# Drivers.net
KiCad netlist of a schematic drawn in Altium Designer
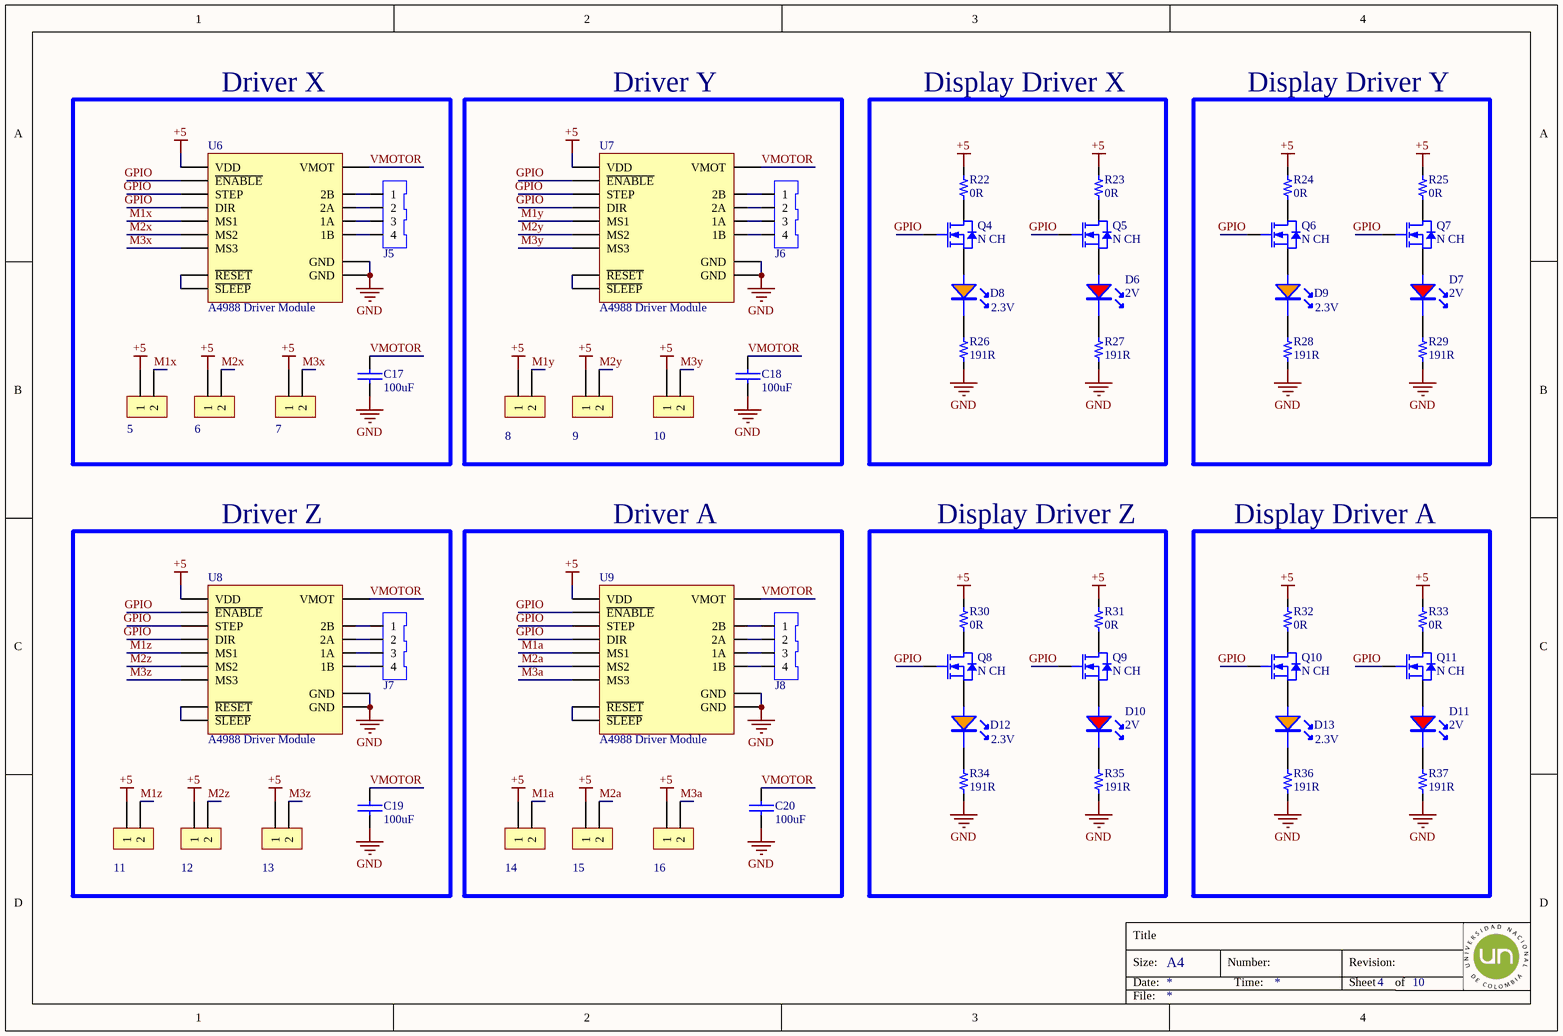
[diagram p0: Drivers.SchDoc]

(export (version "E")
  (design (tool "Eeschema 10.0.6"))
  (components
    (comp (ref "5")
      (value "2x1")
      (footprint "H_2x1_TH_100mil")
      (description "H_Male_2x1_TH_100mil")
      (libsource (lib "CNCLib") (part "H_Male_2x1_TH_100mil"))
    )
    (comp (ref "6")
      (value "2x1")
      (footprint "H_2x1_TH_100mil")
      (description "H_Male_2x1_TH_100mil")
      (libsource (lib "CNCLib") (part "H_Male_2x1_TH_100mil"))
    )
    (comp (ref "7")
      (value "2x1")
      (footprint "H_2x1_TH_100mil")
      (description "H_Male_2x1_TH_100mil")
      (libsource (lib "CNCLib") (part "H_Male_2x1_TH_100mil"))
    )
    (comp (ref "8")
      (value "2x1")
      (footprint "H_2x1_TH_100mil")
      (description "H_Male_2x1_TH_100mil")
      (libsource (lib "CNCLib") (part "H_Male_2x1_TH_100mil"))
    )
    (comp (ref "9")
      (value "2x1")
      (footprint "H_2x1_TH_100mil")
      (description "H_Male_2x1_TH_100mil")
      (libsource (lib "CNCLib") (part "H_Male_2x1_TH_100mil"))
    )
    (comp (ref "10")
      (value "2x1")
      (footprint "H_2x1_TH_100mil")
      (description "H_Male_2x1_TH_100mil")
      (libsource (lib "CNCLib") (part "H_Male_2x1_TH_100mil"))
    )
    (comp (ref "11")
      (value "2x1")
      (footprint "H_2x1_TH_100mil")
      (description "H_Male_2x1_TH_100mil")
      (libsource (lib "CNCLib") (part "H_Male_2x1_TH_100mil"))
    )
    (comp (ref "12")
      (value "2x1")
      (footprint "H_2x1_TH_100mil")
      (description "H_Male_2x1_TH_100mil")
      (libsource (lib "CNCLib") (part "H_Male_2x1_TH_100mil"))
    )
    (comp (ref "13")
      (value "2x1")
      (footprint "H_2x1_TH_100mil")
      (description "H_Male_2x1_TH_100mil")
      (libsource (lib "CNCLib") (part "H_Male_2x1_TH_100mil"))
    )
    (comp (ref "14")
      (value "2x1")
      (footprint "H_2x1_TH_100mil")
      (description "H_Male_2x1_TH_100mil")
      (libsource (lib "CNCLib") (part "H_Male_2x1_TH_100mil"))
    )
    (comp (ref "15")
      (value "2x1")
      (footprint "H_2x1_TH_100mil")
      (description "H_Male_2x1_TH_100mil")
      (libsource (lib "CNCLib") (part "H_Male_2x1_TH_100mil"))
    )
    (comp (ref "16")
      (value "2x1")
      (footprint "H_2x1_TH_100mil")
      (description "H_Male_2x1_TH_100mil")
      (libsource (lib "CNCLib") (part "H_Male_2x1_TH_100mil"))
    )
    (comp (ref "C17")
      (value "100uF")
      (description "100uF 35V ±20% 69mA@120Hz SMD,D6.3xL7.7mm Aluminum Electrolytic Capacitors RoHS")
      (fields
        (field (name "MANUFACTURER") "ROQANG")
        (field (name "MANUFACTURER PART NUMBER") "RVT1V101M0607")
      )
      (libsource (lib "CNCLib") (part "Cap_100uF_Electr_SMD _35V"))
    )
    (comp (ref "C18")
      (value "100uF")
      (description "100uF 35V ±20% 69mA@120Hz SMD,D6.3xL7.7mm Aluminum Electrolytic Capacitors RoHS")
      (fields
        (field (name "MANUFACTURER") "ROQANG")
        (field (name "MANUFACTURER PART NUMBER") "RVT1V101M0607")
      )
      (libsource (lib "CNCLib") (part "Cap_100uF_Electr_SMD _35V"))
    )
    (comp (ref "C19")
      (value "100uF")
      (description "100uF 35V ±20% 69mA@120Hz SMD,D6.3xL7.7mm Aluminum Electrolytic Capacitors RoHS")
      (fields
        (field (name "MANUFACTURER") "ROQANG")
        (field (name "MANUFACTURER PART NUMBER") "RVT1V101M0607")
      )
      (libsource (lib "CNCLib") (part "Cap_100uF_Electr_SMD _35V"))
    )
    (comp (ref "C20")
      (value "100uF")
      (description "100uF 35V ±20% 69mA@120Hz SMD,D6.3xL7.7mm Aluminum Electrolytic Capacitors RoHS")
      (fields
        (field (name "MANUFACTURER") "ROQANG")
        (field (name "MANUFACTURER PART NUMBER") "RVT1V101M0607")
      )
      (libsource (lib "CNCLib") (part "Cap_100uF_Electr_SMD _35V"))
    )
    (comp (ref "D6")
      (value "2V")
      (footprint "0805_LED")
      (description "LED RED CLEAR 0805 SMD")
      (fields
        (field (name "MANUFACTURER") "XINGLIGHT")
        (field (name "MANUFACTURER PART NUMBER") "XL-2012SURC")
      )
      (libsource (lib "CNCLib") (part "LED_0805_RED"))
    )
    (comp (ref "D7")
      (value "2V")
      (footprint "0805_LED")
      (description "LED RED CLEAR 0805 SMD")
      (fields
        (field (name "MANUFACTURER") "XINGLIGHT")
        (field (name "MANUFACTURER PART NUMBER") "XL-2012SURC")
      )
      (libsource (lib "CNCLib") (part "LED_0805_RED"))
    )
    (comp (ref "D8")
      (value "2.3V")
      (footprint "0805_LED")
      (description "LED ORANGE WATER CLEAR 0805 SMD")
      (fields
        (field (name "MANUFACTURER") "XINGLIGHT")
        (field (name "MANUFACTURER PART NUMBER") "XL-2012UOC")
      )
      (libsource (lib "CNCLib") (part "LED_0805_Orange"))
    )
    (comp (ref "D9")
      (value "2.3V")
      (footprint "0805_LED")
      (description "LED ORANGE WATER CLEAR 0805 SMD")
      (fields
        (field (name "MANUFACTURER") "XINGLIGHT")
        (field (name "MANUFACTURER PART NUMBER") "XL-2012UOC")
      )
      (libsource (lib "CNCLib") (part "LED_0805_Orange"))
    )
    (comp (ref "D10")
      (value "2V")
      (footprint "0805_LED")
      (description "LED RED CLEAR 0805 SMD")
      (fields
        (field (name "MANUFACTURER") "XINGLIGHT")
        (field (name "MANUFACTURER PART NUMBER") "XL-2012SURC")
      )
      (libsource (lib "CNCLib") (part "LED_0805_RED"))
    )
    (comp (ref "D11")
      (value "2V")
      (footprint "0805_LED")
      (description "LED RED CLEAR 0805 SMD")
      (fields
        (field (name "MANUFACTURER") "XINGLIGHT")
        (field (name "MANUFACTURER PART NUMBER") "XL-2012SURC")
      )
      (libsource (lib "CNCLib") (part "LED_0805_RED"))
    )
    (comp (ref "D12")
      (value "2.3V")
      (footprint "0805_LED")
      (description "LED ORANGE WATER CLEAR 0805 SMD")
      (fields
        (field (name "MANUFACTURER") "XINGLIGHT")
        (field (name "MANUFACTURER PART NUMBER") "XL-2012UOC")
      )
      (libsource (lib "CNCLib") (part "LED_0805_Orange"))
    )
    (comp (ref "D13")
      (value "2.3V")
      (footprint "0805_LED")
      (description "LED ORANGE WATER CLEAR 0805 SMD")
      (fields
        (field (name "MANUFACTURER") "XINGLIGHT")
        (field (name "MANUFACTURER PART NUMBER") "XL-2012UOC")
      )
      (libsource (lib "CNCLib") (part "LED_0805_Orange"))
    )
    (comp (ref "J5")
      (value "CONN HEADER TH 4POS 2.5mm")
      (fields
        (field (name "MANUFACTURER") "JST")
        (field (name "MANUFACTURER PART NUMBER") "B4B-XH-A(LF)(SN)")
      )
      (libsource (lib "CNCLib") (part "Connector JST 4pin"))
    )
    (comp (ref "J6")
      (value "CONN HEADER TH 4POS 2.5mm")
      (fields
        (field (name "MANUFACTURER") "JST")
        (field (name "MANUFACTURER PART NUMBER") "B4B-XH-A(LF)(SN)")
      )
      (libsource (lib "CNCLib") (part "Connector JST 4pin"))
    )
    (comp (ref "J7")
      (value "CONN HEADER TH 4POS 2.5mm")
      (fields
        (field (name "MANUFACTURER") "JST")
        (field (name "MANUFACTURER PART NUMBER") "B4B-XH-A(LF)(SN)")
      )
      (libsource (lib "CNCLib") (part "Connector JST 4pin"))
    )
    (comp (ref "J8")
      (value "CONN HEADER TH 4POS 2.5mm")
      (fields
        (field (name "MANUFACTURER") "JST")
        (field (name "MANUFACTURER PART NUMBER") "B4B-XH-A(LF)(SN)")
      )
      (libsource (lib "CNCLib") (part "Connector JST 4pin"))
    )
    (comp (ref "Q4")
      (value "N CH")
      (footprint "SOT_23_3")
      (description "MOSFET N-CH 50V 200mA SOT-23")
      (fields (field (name "MANUFACTURER") "onsemi") (field (name "MANUFACTURER PART NUMBER") "BSS138LT1G"))
      (libsource (lib "CNCLib") (part "Q_NFET_50V_200mA_SOT23"))
    )
    (comp (ref "Q5")
      (value "N CH")
      (footprint "SOT_23_3")
      (description "MOSFET N-CH 50V 200mA SOT-23")
      (fields (field (name "MANUFACTURER") "onsemi") (field (name "MANUFACTURER PART NUMBER") "BSS138LT1G"))
      (libsource (lib "CNCLib") (part "Q_NFET_50V_200mA_SOT23"))
    )
    (comp (ref "Q6")
      (value "N CH")
      (footprint "SOT_23_3")
      (description "MOSFET N-CH 50V 200mA SOT-23")
      (fields (field (name "MANUFACTURER") "onsemi") (field (name "MANUFACTURER PART NUMBER") "BSS138LT1G"))
      (libsource (lib "CNCLib") (part "Q_NFET_50V_200mA_SOT23"))
    )
    (comp (ref "Q7")
      (value "N CH")
      (footprint "SOT_23_3")
      (description "MOSFET N-CH 50V 200mA SOT-23")
      (fields (field (name "MANUFACTURER") "onsemi") (field (name "MANUFACTURER PART NUMBER") "BSS138LT1G"))
      (libsource (lib "CNCLib") (part "Q_NFET_50V_200mA_SOT23"))
    )
    (comp (ref "Q8")
      (value "N CH")
      (footprint "SOT_23_3")
      (description "MOSFET N-CH 50V 200mA SOT-23")
      (fields (field (name "MANUFACTURER") "onsemi") (field (name "MANUFACTURER PART NUMBER") "BSS138LT1G"))
      (libsource (lib "CNCLib") (part "Q_NFET_50V_200mA_SOT23"))
    )
    (comp (ref "Q9")
      (value "N CH")
      (footprint "SOT_23_3")
      (description "MOSFET N-CH 50V 200mA SOT-23")
      (fields (field (name "MANUFACTURER") "onsemi") (field (name "MANUFACTURER PART NUMBER") "BSS138LT1G"))
      (libsource (lib "CNCLib") (part "Q_NFET_50V_200mA_SOT23"))
    )
    (comp (ref "Q10")
      (value "N CH")
      (footprint "SOT_23_3")
      (description "MOSFET N-CH 50V 200mA SOT-23")
      (fields (field (name "MANUFACTURER") "onsemi") (field (name "MANUFACTURER PART NUMBER") "BSS138LT1G"))
      (libsource (lib "CNCLib") (part "Q_NFET_50V_200mA_SOT23"))
    )
    (comp (ref "Q11")
      (value "N CH")
      (footprint "SOT_23_3")
      (description "MOSFET N-CH 50V 200mA SOT-23")
      (fields (field (name "MANUFACTURER") "onsemi") (field (name "MANUFACTURER PART NUMBER") "BSS138LT1G"))
      (libsource (lib "CNCLib") (part "Q_NFET_50V_200mA_SOT23"))
    )
    (comp (ref "R22")
      (value "0R")
      (footprint "0603_res")
      (description "RES SMD 0R OHM 5% 1/10W 0603")
      (fields
        (field (name "MANUFACTURER") "FOJAN")
        (field (name "MANUFACTURER PART NUMBER") "FRC0603P000 TS")
      )
      (libsource (lib "CNCLib") (part "Res_0R_0603_1/10W"))
    )
    (comp (ref "R23")
      (value "0R")
      (footprint "0603_res")
      (description "RES SMD 0R OHM 5% 1/10W 0603")
      (fields
        (field (name "MANUFACTURER") "FOJAN")
        (field (name "MANUFACTURER PART NUMBER") "FRC0603P000 TS")
      )
      (libsource (lib "CNCLib") (part "Res_0R_0603_1/10W"))
    )
    (comp (ref "R24")
      (value "0R")
      (footprint "0603_res")
      (description "RES SMD 0R OHM 5% 1/10W 0603")
      (fields
        (field (name "MANUFACTURER") "FOJAN")
        (field (name "MANUFACTURER PART NUMBER") "FRC0603P000 TS")
      )
      (libsource (lib "CNCLib") (part "Res_0R_0603_1/10W"))
    )
    (comp (ref "R25")
      (value "0R")
      (footprint "0603_res")
      (description "RES SMD 0R OHM 5% 1/10W 0603")
      (fields
        (field (name "MANUFACTURER") "FOJAN")
        (field (name "MANUFACTURER PART NUMBER") "FRC0603P000 TS")
      )
      (libsource (lib "CNCLib") (part "Res_0R_0603_1/10W"))
    )
    (comp (ref "R26")
      (value "191R")
      (footprint "0603_res")
      (description "100mW Thick Film Resistor 75V ±100ppm/℃ ±1% 191Ω 0603 Chip Resistor - Surface Mount ROHS")
      (fields
        (field (name "MANUFACTURER") "FOJAN")
        (field (name "MANUFACTURER PART NUMBER") "FRC0603F1910TS")
      )
      (libsource (lib "CNCLib") (part "Res_191R_0603_1/10W"))
    )
    (comp (ref "R27")
      (value "191R")
      (footprint "0603_res")
      (description "100mW Thick Film Resistor 75V ±100ppm/℃ ±1% 191Ω 0603 Chip Resistor - Surface Mount ROHS")
      (fields
        (field (name "MANUFACTURER") "FOJAN")
        (field (name "MANUFACTURER PART NUMBER") "FRC0603F1910TS")
      )
      (libsource (lib "CNCLib") (part "Res_191R_0603_1/10W"))
    )
    (comp (ref "R28")
      (value "191R")
      (footprint "0603_res")
      (description "100mW Thick Film Resistor 75V ±100ppm/℃ ±1% 191Ω 0603 Chip Resistor - Surface Mount ROHS")
      (fields
        (field (name "MANUFACTURER") "FOJAN")
        (field (name "MANUFACTURER PART NUMBER") "FRC0603F1910TS")
      )
      (libsource (lib "CNCLib") (part "Res_191R_0603_1/10W"))
    )
    (comp (ref "R29")
      (value "191R")
      (footprint "0603_res")
      (description "100mW Thick Film Resistor 75V ±100ppm/℃ ±1% 191Ω 0603 Chip Resistor - Surface Mount ROHS")
      (fields
        (field (name "MANUFACTURER") "FOJAN")
        (field (name "MANUFACTURER PART NUMBER") "FRC0603F1910TS")
      )
      (libsource (lib "CNCLib") (part "Res_191R_0603_1/10W"))
    )
    (comp (ref "R30")
      (value "0R")
      (footprint "0603_res")
      (description "RES SMD 0R OHM 5% 1/10W 0603")
      (fields
        (field (name "MANUFACTURER") "FOJAN")
        (field (name "MANUFACTURER PART NUMBER") "FRC0603P000 TS")
      )
      (libsource (lib "CNCLib") (part "Res_0R_0603_1/10W"))
    )
    (comp (ref "R31")
      (value "0R")
      (footprint "0603_res")
      (description "RES SMD 0R OHM 5% 1/10W 0603")
      (fields
        (field (name "MANUFACTURER") "FOJAN")
        (field (name "MANUFACTURER PART NUMBER") "FRC0603P000 TS")
      )
      (libsource (lib "CNCLib") (part "Res_0R_0603_1/10W"))
    )
    (comp (ref "R32")
      (value "0R")
      (footprint "0603_res")
      (description "RES SMD 0R OHM 5% 1/10W 0603")
      (fields
        (field (name "MANUFACTURER") "FOJAN")
        (field (name "MANUFACTURER PART NUMBER") "FRC0603P000 TS")
      )
      (libsource (lib "CNCLib") (part "Res_0R_0603_1/10W"))
    )
    (comp (ref "R33")
      (value "0R")
      (footprint "0603_res")
      (description "RES SMD 0R OHM 5% 1/10W 0603")
      (fields
        (field (name "MANUFACTURER") "FOJAN")
        (field (name "MANUFACTURER PART NUMBER") "FRC0603P000 TS")
      )
      (libsource (lib "CNCLib") (part "Res_0R_0603_1/10W"))
    )
    (comp (ref "R34")
      (value "191R")
      (footprint "0603_res")
      (description "100mW Thick Film Resistor 75V ±100ppm/℃ ±1% 191Ω 0603 Chip Resistor - Surface Mount ROHS")
      (fields
        (field (name "MANUFACTURER") "FOJAN")
        (field (name "MANUFACTURER PART NUMBER") "FRC0603F1910TS")
      )
      (libsource (lib "CNCLib") (part "Res_191R_0603_1/10W"))
    )
    (comp (ref "R35")
      (value "191R")
      (footprint "0603_res")
      (description "100mW Thick Film Resistor 75V ±100ppm/℃ ±1% 191Ω 0603 Chip Resistor - Surface Mount ROHS")
      (fields
        (field (name "MANUFACTURER") "FOJAN")
        (field (name "MANUFACTURER PART NUMBER") "FRC0603F1910TS")
      )
      (libsource (lib "CNCLib") (part "Res_191R_0603_1/10W"))
    )
    (comp (ref "R36")
      (value "191R")
      (footprint "0603_res")
      (description "100mW Thick Film Resistor 75V ±100ppm/℃ ±1% 191Ω 0603 Chip Resistor - Surface Mount ROHS")
      (fields
        (field (name "MANUFACTURER") "FOJAN")
        (field (name "MANUFACTURER PART NUMBER") "FRC0603F1910TS")
      )
      (libsource (lib "CNCLib") (part "Res_191R_0603_1/10W"))
    )
    (comp (ref "R37")
      (value "191R")
      (footprint "0603_res")
      (description "100mW Thick Film Resistor 75V ±100ppm/℃ ±1% 191Ω 0603 Chip Resistor - Surface Mount ROHS")
      (fields
        (field (name "MANUFACTURER") "FOJAN")
        (field (name "MANUFACTURER PART NUMBER") "FRC0603F1910TS")
      )
      (libsource (lib "CNCLib") (part "Res_191R_0603_1/10W"))
    )
    (comp (ref "U6") (value "A4988 Driver Module") (libsource (lib "CNCLib") (part "A4988 Driver Module")))
    (comp (ref "U7") (value "A4988 Driver Module") (libsource (lib "CNCLib") (part "A4988 Driver Module")))
    (comp (ref "U8") (value "A4988 Driver Module") (libsource (lib "CNCLib") (part "A4988 Driver Module")))
    (comp (ref "U9") (value "A4988 Driver Module") (libsource (lib "CNCLib") (part "A4988 Driver Module")))
  )
  (nets
    (net (code "1") (name "+5") (class "Default")
      (node (ref "10") (pin "1") (pinfunction "1_1") (pintype "passive"))
      (node (ref "11") (pin "1") (pinfunction "1_1") (pintype "passive"))
      (node (ref "12") (pin "1") (pinfunction "1_1") (pintype "passive"))
      (node (ref "13") (pin "1") (pinfunction "1_1") (pintype "passive"))
      (node (ref "14") (pin "1") (pinfunction "1_1") (pintype "passive"))
      (node (ref "15") (pin "1") (pinfunction "1_1") (pintype "passive"))
      (node (ref "16") (pin "1") (pinfunction "1_1") (pintype "passive"))
      (node (ref "5") (pin "1") (pinfunction "1_1") (pintype "passive"))
      (node (ref "6") (pin "1") (pinfunction "1_1") (pintype "passive"))
      (node (ref "7") (pin "1") (pinfunction "1_1") (pintype "passive"))
      (node (ref "8") (pin "1") (pinfunction "1_1") (pintype "passive"))
      (node (ref "9") (pin "1") (pinfunction "1_1") (pintype "passive"))
      (node (ref "R22") (pin "2") (pinfunction "2_2") (pintype "passive"))
      (node (ref "R23") (pin "2") (pinfunction "2_2") (pintype "passive"))
      (node (ref "R24") (pin "2") (pinfunction "2_2") (pintype "passive"))
      (node (ref "R25") (pin "2") (pinfunction "2_2") (pintype "passive"))
      (node (ref "R30") (pin "2") (pinfunction "2_2") (pintype "passive"))
      (node (ref "R31") (pin "2") (pinfunction "2_2") (pintype "passive"))
      (node (ref "R32") (pin "2") (pinfunction "2_2") (pintype "passive"))
      (node (ref "R33") (pin "2") (pinfunction "2_2") (pintype "passive"))
      (node (ref "U6") (pin "15") (pinfunction "VDD_15") (pintype "passive"))
      (node (ref "U7") (pin "15") (pinfunction "VDD_15") (pintype "passive"))
      (node (ref "U8") (pin "15") (pinfunction "VDD_15") (pintype "passive"))
      (node (ref "U9") (pin "15") (pinfunction "VDD_15") (pintype "passive"))
    )
    (net (code "2") (name "/GPIO") (class "Default")
      (node (ref "Q10") (pin "1") (pinfunction "G_1") (pintype "passive"))
      (node (ref "Q11") (pin "1") (pinfunction "G_1") (pintype "passive"))
      (node (ref "Q4") (pin "1") (pinfunction "G_1") (pintype "passive"))
      (node (ref "Q5") (pin "1") (pinfunction "G_1") (pintype "passive"))
      (node (ref "Q6") (pin "1") (pinfunction "G_1") (pintype "passive"))
      (node (ref "Q7") (pin "1") (pinfunction "G_1") (pintype "passive"))
      (node (ref "Q8") (pin "1") (pinfunction "G_1") (pintype "passive"))
      (node (ref "Q9") (pin "1") (pinfunction "G_1") (pintype "passive"))
      (node (ref "U6") (pin "1") (pinfunction "~{ENABLE}_1") (pintype "passive"))
      (node (ref "U6") (pin "7") (pinfunction "STEP_7") (pintype "passive"))
      (node (ref "U6") (pin "8") (pinfunction "DIR_8") (pintype "passive"))
      (node (ref "U7") (pin "1") (pinfunction "~{ENABLE}_1") (pintype "passive"))
      (node (ref "U7") (pin "7") (pinfunction "STEP_7") (pintype "passive"))
      (node (ref "U7") (pin "8") (pinfunction "DIR_8") (pintype "passive"))
      (node (ref "U8") (pin "1") (pinfunction "~{ENABLE}_1") (pintype "passive"))
      (node (ref "U8") (pin "7") (pinfunction "STEP_7") (pintype "passive"))
      (node (ref "U8") (pin "8") (pinfunction "DIR_8") (pintype "passive"))
      (node (ref "U9") (pin "1") (pinfunction "~{ENABLE}_1") (pintype "passive"))
      (node (ref "U9") (pin "7") (pinfunction "STEP_7") (pintype "passive"))
      (node (ref "U9") (pin "8") (pinfunction "DIR_8") (pintype "passive"))
    )
    (net (code "3") (name "/M1a") (class "Default")
      (node (ref "14") (pin "2") (pinfunction "2_2") (pintype "passive"))
      (node (ref "U9") (pin "2") (pinfunction "MS1_2") (pintype "passive"))
    )
    (net (code "4") (name "/M1x") (class "Default")
      (node (ref "5") (pin "2") (pinfunction "2_2") (pintype "passive"))
      (node (ref "U6") (pin "2") (pinfunction "MS1_2") (pintype "passive"))
    )
    (net (code "5") (name "/M1y") (class "Default")
      (node (ref "8") (pin "2") (pinfunction "2_2") (pintype "passive"))
      (node (ref "U7") (pin "2") (pinfunction "MS1_2") (pintype "passive"))
    )
    (net (code "6") (name "/M1z") (class "Default")
      (node (ref "11") (pin "2") (pinfunction "2_2") (pintype "passive"))
      (node (ref "U8") (pin "2") (pinfunction "MS1_2") (pintype "passive"))
    )
    (net (code "7") (name "/M2a") (class "Default")
      (node (ref "15") (pin "2") (pinfunction "2_2") (pintype "passive"))
      (node (ref "U9") (pin "3") (pinfunction "MS2_3") (pintype "passive"))
    )
    (net (code "8") (name "/M2x") (class "Default")
      (node (ref "6") (pin "2") (pinfunction "2_2") (pintype "passive"))
      (node (ref "U6") (pin "3") (pinfunction "MS2_3") (pintype "passive"))
    )
    (net (code "9") (name "/M2y") (class "Default")
      (node (ref "9") (pin "2") (pinfunction "2_2") (pintype "passive"))
      (node (ref "U7") (pin "3") (pinfunction "MS2_3") (pintype "passive"))
    )
    (net (code "10") (name "/M2z") (class "Default")
      (node (ref "12") (pin "2") (pinfunction "2_2") (pintype "passive"))
      (node (ref "U8") (pin "3") (pinfunction "MS2_3") (pintype "passive"))
    )
    (net (code "11") (name "/M3a") (class "Default")
      (node (ref "16") (pin "2") (pinfunction "2_2") (pintype "passive"))
      (node (ref "U9") (pin "4") (pinfunction "MS3_4") (pintype "passive"))
    )
    (net (code "12") (name "/M3x") (class "Default")
      (node (ref "7") (pin "2") (pinfunction "2_2") (pintype "passive"))
      (node (ref "U6") (pin "4") (pinfunction "MS3_4") (pintype "passive"))
    )
    (net (code "13") (name "/M3y") (class "Default")
      (node (ref "10") (pin "2") (pinfunction "2_2") (pintype "passive"))
      (node (ref "U7") (pin "4") (pinfunction "MS3_4") (pintype "passive"))
    )
    (net (code "14") (name "/M3z") (class "Default")
      (node (ref "13") (pin "2") (pinfunction "2_2") (pintype "passive"))
      (node (ref "U8") (pin "4") (pinfunction "MS3_4") (pintype "passive"))
    )
    (net (code "15") (name "/VMOTOR") (class "Default")
      (node (ref "C17") (pin "1") (pinfunction "1_1") (pintype "passive"))
      (node (ref "C18") (pin "1") (pinfunction "1_1") (pintype "passive"))
      (node (ref "C19") (pin "1") (pinfunction "1_1") (pintype "passive"))
      (node (ref "C20") (pin "1") (pinfunction "1_1") (pintype "passive"))
      (node (ref "U6") (pin "9") (pinfunction "VMOT_9") (pintype "passive"))
      (node (ref "U7") (pin "9") (pinfunction "VMOT_9") (pintype "passive"))
      (node (ref "U8") (pin "9") (pinfunction "VMOT_9") (pintype "passive"))
      (node (ref "U9") (pin "9") (pinfunction "VMOT_9") (pintype "passive"))
    )
    (net (code "16") (name "GND") (class "Default")
      (node (ref "C17") (pin "2") (pinfunction "2_2") (pintype "passive"))
      (node (ref "C18") (pin "2") (pinfunction "2_2") (pintype "passive"))
      (node (ref "C19") (pin "2") (pinfunction "2_2") (pintype "passive"))
      (node (ref "C20") (pin "2") (pinfunction "2_2") (pintype "passive"))
      (node (ref "R26") (pin "1") (pinfunction "1_1") (pintype "passive"))
      (node (ref "R27") (pin "1") (pinfunction "1_1") (pintype "passive"))
      (node (ref "R28") (pin "1") (pinfunction "1_1") (pintype "passive"))
      (node (ref "R29") (pin "1") (pinfunction "1_1") (pintype "passive"))
      (node (ref "R34") (pin "1") (pinfunction "1_1") (pintype "passive"))
      (node (ref "R35") (pin "1") (pinfunction "1_1") (pintype "passive"))
      (node (ref "R36") (pin "1") (pinfunction "1_1") (pintype "passive"))
      (node (ref "R37") (pin "1") (pinfunction "1_1") (pintype "passive"))
      (node (ref "U6") (pin "10") (pinfunction "GND_10") (pintype "passive"))
      (node (ref "U6") (pin "16") (pinfunction "GND_16") (pintype "passive"))
      (node (ref "U7") (pin "10") (pinfunction "GND_10") (pintype "passive"))
      (node (ref "U7") (pin "16") (pinfunction "GND_16") (pintype "passive"))
      (node (ref "U8") (pin "10") (pinfunction "GND_10") (pintype "passive"))
      (node (ref "U8") (pin "16") (pinfunction "GND_16") (pintype "passive"))
      (node (ref "U9") (pin "10") (pinfunction "GND_10") (pintype "passive"))
      (node (ref "U9") (pin "16") (pinfunction "GND_16") (pintype "passive"))
    )
    (net (code "17") (name "Net-(D6-A)") (class "Default")
      (node (ref "D6") (pin "1") (pinfunction "A_1") (pintype "passive"))
      (node (ref "Q5") (pin "2") (pinfunction "S_2") (pintype "passive"))
    )
    (net (code "18") (name "Net-(D6-Pad2)") (class "Default")
      (node (ref "D6") (pin "2") (pinfunction "2_2") (pintype "passive"))
      (node (ref "R27") (pin "2") (pinfunction "2_2") (pintype "passive"))
    )
    (net (code "19") (name "Net-(D7-A)") (class "Default")
      (node (ref "D7") (pin "1") (pinfunction "A_1") (pintype "passive"))
      (node (ref "Q7") (pin "2") (pinfunction "S_2") (pintype "passive"))
    )
    (net (code "20") (name "Net-(D7-Pad2)") (class "Default")
      (node (ref "D7") (pin "2") (pinfunction "2_2") (pintype "passive"))
      (node (ref "R29") (pin "2") (pinfunction "2_2") (pintype "passive"))
    )
    (net (code "21") (name "Net-(D8-A)") (class "Default")
      (node (ref "D8") (pin "1") (pinfunction "A_1") (pintype "passive"))
      (node (ref "Q4") (pin "2") (pinfunction "S_2") (pintype "passive"))
    )
    (net (code "22") (name "Net-(D8-Pad2)") (class "Default")
      (node (ref "D8") (pin "2") (pinfunction "2_2") (pintype "passive"))
      (node (ref "R26") (pin "2") (pinfunction "2_2") (pintype "passive"))
    )
    (net (code "23") (name "Net-(D9-A)") (class "Default")
      (node (ref "D9") (pin "1") (pinfunction "A_1") (pintype "passive"))
      (node (ref "Q6") (pin "2") (pinfunction "S_2") (pintype "passive"))
    )
    (net (code "24") (name "Net-(D9-Pad2)") (class "Default")
      (node (ref "D9") (pin "2") (pinfunction "2_2") (pintype "passive"))
      (node (ref "R28") (pin "2") (pinfunction "2_2") (pintype "passive"))
    )
    (net (code "25") (name "Net-(D10-A)") (class "Default")
      (node (ref "D10") (pin "1") (pinfunction "A_1") (pintype "passive"))
      (node (ref "Q9") (pin "2") (pinfunction "S_2") (pintype "passive"))
    )
    (net (code "26") (name "Net-(D10-Pad2)") (class "Default")
      (node (ref "D10") (pin "2") (pinfunction "2_2") (pintype "passive"))
      (node (ref "R35") (pin "2") (pinfunction "2_2") (pintype "passive"))
    )
    (net (code "27") (name "Net-(D11-A)") (class "Default")
      (node (ref "D11") (pin "1") (pinfunction "A_1") (pintype "passive"))
      (node (ref "Q11") (pin "2") (pinfunction "S_2") (pintype "passive"))
    )
    (net (code "28") (name "Net-(D11-Pad2)") (class "Default")
      (node (ref "D11") (pin "2") (pinfunction "2_2") (pintype "passive"))
      (node (ref "R37") (pin "2") (pinfunction "2_2") (pintype "passive"))
    )
    (net (code "29") (name "Net-(D12-A)") (class "Default")
      (node (ref "D12") (pin "1") (pinfunction "A_1") (pintype "passive"))
      (node (ref "Q8") (pin "2") (pinfunction "S_2") (pintype "passive"))
    )
    (net (code "30") (name "Net-(D12-Pad2)") (class "Default")
      (node (ref "D12") (pin "2") (pinfunction "2_2") (pintype "passive"))
      (node (ref "R34") (pin "2") (pinfunction "2_2") (pintype "passive"))
    )
    (net (code "31") (name "Net-(D13-A)") (class "Default")
      (node (ref "D13") (pin "1") (pinfunction "A_1") (pintype "passive"))
      (node (ref "Q10") (pin "2") (pinfunction "S_2") (pintype "passive"))
    )
    (net (code "32") (name "Net-(D13-Pad2)") (class "Default")
      (node (ref "D13") (pin "2") (pinfunction "2_2") (pintype "passive"))
      (node (ref "R36") (pin "2") (pinfunction "2_2") (pintype "passive"))
    )
    (net (code "33") (name "Net-(Q4-D)") (class "Default")
      (node (ref "Q4") (pin "3") (pinfunction "D_3") (pintype "passive"))
      (node (ref "R22") (pin "1") (pinfunction "1_1") (pintype "passive"))
    )
    (net (code "34") (name "Net-(Q5-D)") (class "Default")
      (node (ref "Q5") (pin "3") (pinfunction "D_3") (pintype "passive"))
      (node (ref "R23") (pin "1") (pinfunction "1_1") (pintype "passive"))
    )
    (net (code "35") (name "Net-(Q6-D)") (class "Default")
      (node (ref "Q6") (pin "3") (pinfunction "D_3") (pintype "passive"))
      (node (ref "R24") (pin "1") (pinfunction "1_1") (pintype "passive"))
    )
    (net (code "36") (name "Net-(Q7-D)") (class "Default")
      (node (ref "Q7") (pin "3") (pinfunction "D_3") (pintype "passive"))
      (node (ref "R25") (pin "1") (pinfunction "1_1") (pintype "passive"))
    )
    (net (code "37") (name "Net-(Q8-D)") (class "Default")
      (node (ref "Q8") (pin "3") (pinfunction "D_3") (pintype "passive"))
      (node (ref "R30") (pin "1") (pinfunction "1_1") (pintype "passive"))
    )
    (net (code "38") (name "Net-(Q9-D)") (class "Default")
      (node (ref "Q9") (pin "3") (pinfunction "D_3") (pintype "passive"))
      (node (ref "R31") (pin "1") (pinfunction "1_1") (pintype "passive"))
    )
    (net (code "39") (name "Net-(Q10-D)") (class "Default")
      (node (ref "Q10") (pin "3") (pinfunction "D_3") (pintype "passive"))
      (node (ref "R32") (pin "1") (pinfunction "1_1") (pintype "passive"))
    )
    (net (code "40") (name "Net-(Q11-D)") (class "Default")
      (node (ref "Q11") (pin "3") (pinfunction "D_3") (pintype "passive"))
      (node (ref "R33") (pin "1") (pinfunction "1_1") (pintype "passive"))
    )
    (net (code "41") (name "Net-(U6-1A)") (class "Default")
      (node (ref "J5") (pin "3") (pinfunction "3_3") (pintype "passive"))
      (node (ref "U6") (pin "13") (pinfunction "1A_13") (pintype "passive"))
    )
    (net (code "42") (name "Net-(U6-1B)") (class "Default")
      (node (ref "J5") (pin "4") (pinfunction "4_4") (pintype "passive"))
      (node (ref "U6") (pin "14") (pinfunction "1B_14") (pintype "passive"))
    )
    (net (code "43") (name "Net-(U6-2A)") (class "Default")
      (node (ref "J5") (pin "2") (pinfunction "2_2") (pintype "passive"))
      (node (ref "U6") (pin "12") (pinfunction "2A_12") (pintype "passive"))
    )
    (net (code "44") (name "Net-(U6-2B)") (class "Default")
      (node (ref "J5") (pin "1") (pinfunction "1_1") (pintype "passive"))
      (node (ref "U6") (pin "11") (pinfunction "2B_11") (pintype "passive"))
    )
    (net (code "45") (name "Net-(U6-~{RESET})") (class "Default")
      (node (ref "U6") (pin "5") (pinfunction "~{RESET}_5") (pintype "passive"))
      (node (ref "U6") (pin "6") (pinfunction "~{SLEEP}_6") (pintype "passive"))
    )
    (net (code "46") (name "Net-(U7-1A)") (class "Default")
      (node (ref "J6") (pin "3") (pinfunction "3_3") (pintype "passive"))
      (node (ref "U7") (pin "13") (pinfunction "1A_13") (pintype "passive"))
    )
    (net (code "47") (name "Net-(U7-1B)") (class "Default")
      (node (ref "J6") (pin "4") (pinfunction "4_4") (pintype "passive"))
      (node (ref "U7") (pin "14") (pinfunction "1B_14") (pintype "passive"))
    )
    (net (code "48") (name "Net-(U7-2A)") (class "Default")
      (node (ref "J6") (pin "2") (pinfunction "2_2") (pintype "passive"))
      (node (ref "U7") (pin "12") (pinfunction "2A_12") (pintype "passive"))
    )
    (net (code "49") (name "Net-(U7-2B)") (class "Default")
      (node (ref "J6") (pin "1") (pinfunction "1_1") (pintype "passive"))
      (node (ref "U7") (pin "11") (pinfunction "2B_11") (pintype "passive"))
    )
    (net (code "50") (name "Net-(U7-~{RESET})") (class "Default")
      (node (ref "U7") (pin "5") (pinfunction "~{RESET}_5") (pintype "passive"))
      (node (ref "U7") (pin "6") (pinfunction "~{SLEEP}_6") (pintype "passive"))
    )
    (net (code "51") (name "Net-(U8-1A)") (class "Default")
      (node (ref "J7") (pin "3") (pinfunction "3_3") (pintype "passive"))
      (node (ref "U8") (pin "13") (pinfunction "1A_13") (pintype "passive"))
    )
    (net (code "52") (name "Net-(U8-1B)") (class "Default")
      (node (ref "J7") (pin "4") (pinfunction "4_4") (pintype "passive"))
      (node (ref "U8") (pin "14") (pinfunction "1B_14") (pintype "passive"))
    )
    (net (code "53") (name "Net-(U8-2A)") (class "Default")
      (node (ref "J7") (pin "2") (pinfunction "2_2") (pintype "passive"))
      (node (ref "U8") (pin "12") (pinfunction "2A_12") (pintype "passive"))
    )
    (net (code "54") (name "Net-(U8-2B)") (class "Default")
      (node (ref "J7") (pin "1") (pinfunction "1_1") (pintype "passive"))
      (node (ref "U8") (pin "11") (pinfunction "2B_11") (pintype "passive"))
    )
    (net (code "55") (name "Net-(U8-~{RESET})") (class "Default")
      (node (ref "U8") (pin "5") (pinfunction "~{RESET}_5") (pintype "passive"))
      (node (ref "U8") (pin "6") (pinfunction "~{SLEEP}_6") (pintype "passive"))
    )
    (net (code "56") (name "Net-(U9-1A)") (class "Default")
      (node (ref "J8") (pin "3") (pinfunction "3_3") (pintype "passive"))
      (node (ref "U9") (pin "13") (pinfunction "1A_13") (pintype "passive"))
    )
    (net (code "57") (name "Net-(U9-1B)") (class "Default")
      (node (ref "J8") (pin "4") (pinfunction "4_4") (pintype "passive"))
      (node (ref "U9") (pin "14") (pinfunction "1B_14") (pintype "passive"))
    )
    (net (code "58") (name "Net-(U9-2A)") (class "Default")
      (node (ref "J8") (pin "2") (pinfunction "2_2") (pintype "passive"))
      (node (ref "U9") (pin "12") (pinfunction "2A_12") (pintype "passive"))
    )
    (net (code "59") (name "Net-(U9-2B)") (class "Default")
      (node (ref "J8") (pin "1") (pinfunction "1_1") (pintype "passive"))
      (node (ref "U9") (pin "11") (pinfunction "2B_11") (pintype "passive"))
    )
    (net (code "60") (name "Net-(U9-~{RESET})") (class "Default")
      (node (ref "U9") (pin "5") (pinfunction "~{RESET}_5") (pintype "passive"))
      (node (ref "U9") (pin "6") (pinfunction "~{SLEEP}_6") (pintype "passive"))
    )
  )
)
